# Pedal_Back.net
KiCad netlist of a schematic drawn in Altium Designer
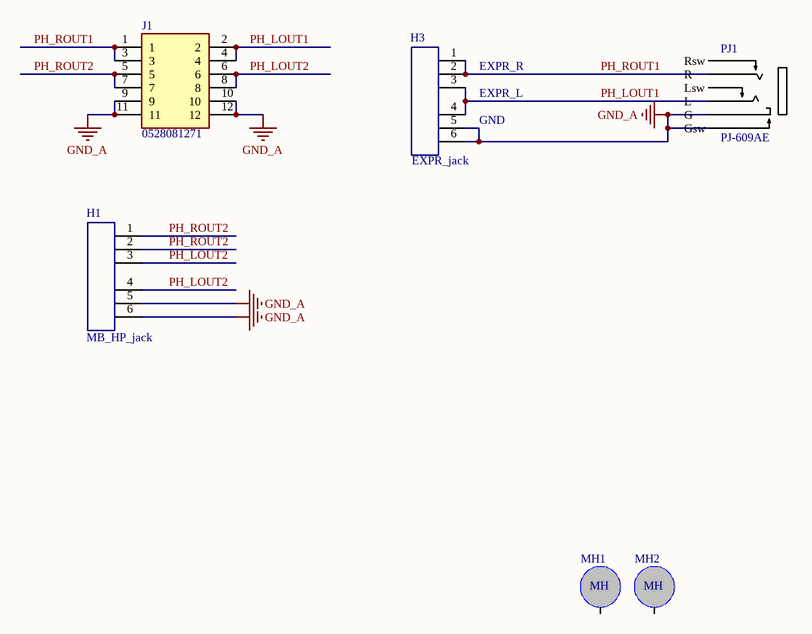
[diagram p0: Pedal_Back.SchDoc]

(export (version "E")
  (design (tool "Eeschema 10.0.6"))
  (components
    (comp (ref "H1")
      (value "MB_HP_jack")
      (footprint "ProtoStack_H750VBT:header-6_male")
      (libsource (lib "ProtoStack_H750VBT") (part "arduino_header_6"))
    )
    (comp (ref "H3")
      (value "EXPR_jack")
      (footprint "ProtoStack_H750VBT:header-6_male")
      (libsource (lib "ProtoStack_H750VBT") (part "arduino_header_6"))
    )
    (comp (ref "J1")
      (value "0528081271")
      (footprint "ProtoStack_H750VBT:AFA11-S12GLA-00")
      (description "Connector")
      (libsource (lib "ProtoStack_H750VBT") (part "0528081271"))
    )
    (comp (ref "MH1")
      (value "MountingHole")
      (footprint "ProtoStack_H750VBT:Hole_2.5mm")
      (libsource (lib "ProtoStack_H750VBT") (part "MountingHole"))
    )
    (comp (ref "MH2")
      (value "MountingHole")
      (footprint "ProtoStack_H750VBT:Hole_2.5mm")
      (libsource (lib "ProtoStack_H750VBT") (part "MountingHole"))
    )
    (comp (ref "PJ1")
      (value "PJ-609AE")
      (footprint "ProtoStack_H750VBT:PJ609AE")
      (description "6.3mm jack HOOYA")
      (libsource (lib "ProtoStack_H750VBT") (part "PJ-609AE"))
    )
  )
  (nets
    (net (code "1") (name "/PH_LOUT1") (class "Default")
      (node (ref "H3") (pin "3") (pinfunction "3_3") (pintype "passive"))
      (node (ref "H3") (pin "4") (pinfunction "4_4") (pintype "passive"))
      (node (ref "J1") (pin "2") (pinfunction "2_2") (pintype "passive"))
      (node (ref "J1") (pin "4") (pinfunction "4_4") (pintype "passive"))
      (node (ref "PJ1") (pin "6") (pinfunction "L_6") (pintype "passive"))
    )
    (net (code "2") (name "/PH_LOUT2") (class "Default")
      (node (ref "H1") (pin "3") (pinfunction "3_3") (pintype "passive"))
      (node (ref "H1") (pin "4") (pinfunction "4_4") (pintype "passive"))
      (node (ref "J1") (pin "6") (pinfunction "6_6") (pintype "passive"))
      (node (ref "J1") (pin "8") (pinfunction "8_8") (pintype "passive"))
    )
    (net (code "3") (name "/PH_ROUT1") (class "Default")
      (node (ref "H3") (pin "1") (pinfunction "1_1") (pintype "passive"))
      (node (ref "H3") (pin "2") (pinfunction "2_2") (pintype "passive"))
      (node (ref "J1") (pin "1") (pinfunction "1_1") (pintype "passive"))
      (node (ref "J1") (pin "3") (pinfunction "3_3") (pintype "passive"))
      (node (ref "PJ1") (pin "4") (pinfunction "R_4") (pintype "passive"))
    )
    (net (code "4") (name "/PH_ROUT2") (class "Default")
      (node (ref "H1") (pin "1") (pinfunction "1_1") (pintype "passive"))
      (node (ref "H1") (pin "2") (pinfunction "2_2") (pintype "passive"))
      (node (ref "J1") (pin "5") (pinfunction "5_5") (pintype "passive"))
      (node (ref "J1") (pin "7") (pinfunction "7_7") (pintype "passive"))
    )
    (net (code "5") (name "GND_A") (class "Default")
      (node (ref "H1") (pin "5") (pinfunction "5_5") (pintype "passive"))
      (node (ref "H1") (pin "6") (pinfunction "6_6") (pintype "passive"))
      (node (ref "H3") (pin "5") (pinfunction "5_5") (pintype "passive"))
      (node (ref "H3") (pin "6") (pinfunction "6_6") (pintype "passive"))
      (node (ref "J1") (pin "10") (pinfunction "10_10") (pintype "passive"))
      (node (ref "J1") (pin "11") (pinfunction "11_11") (pintype "passive"))
      (node (ref "J1") (pin "12") (pinfunction "12_12") (pintype "passive"))
      (node (ref "J1") (pin "9") (pinfunction "9_9") (pintype "passive"))
      (node (ref "PJ1") (pin "2") (pinfunction "G_2") (pintype "passive"))
      (node (ref "PJ1") (pin "3") (pinfunction "Gsw_3") (pintype "passive"))
    )
    (net (code "6") (name "unconnected-(MH1-Pad0)") (class "Default")
      (node (ref "MH1") (pin "0") (pinfunction "0_0") (pintype "passive"))
    )
    (net (code "7") (name "unconnected-(MH2-Pad0)") (class "Default")
      (node (ref "MH2") (pin "0") (pinfunction "0_0") (pintype "passive"))
    )
    (net (code "8") (name "unconnected-(PJ1-Lsw-Pad7)") (class "Default")
      (node (ref "PJ1") (pin "7") (pinfunction "Lsw_7") (pintype "passive"))
    )
    (net (code "9") (name "unconnected-(PJ1-Rsw-Pad5)") (class "Default")
      (node (ref "PJ1") (pin "5") (pinfunction "Rsw_5") (pintype "passive"))
    )
  )
)
